# Ethernet.net
KiCad netlist of a schematic drawn in Altium Designer
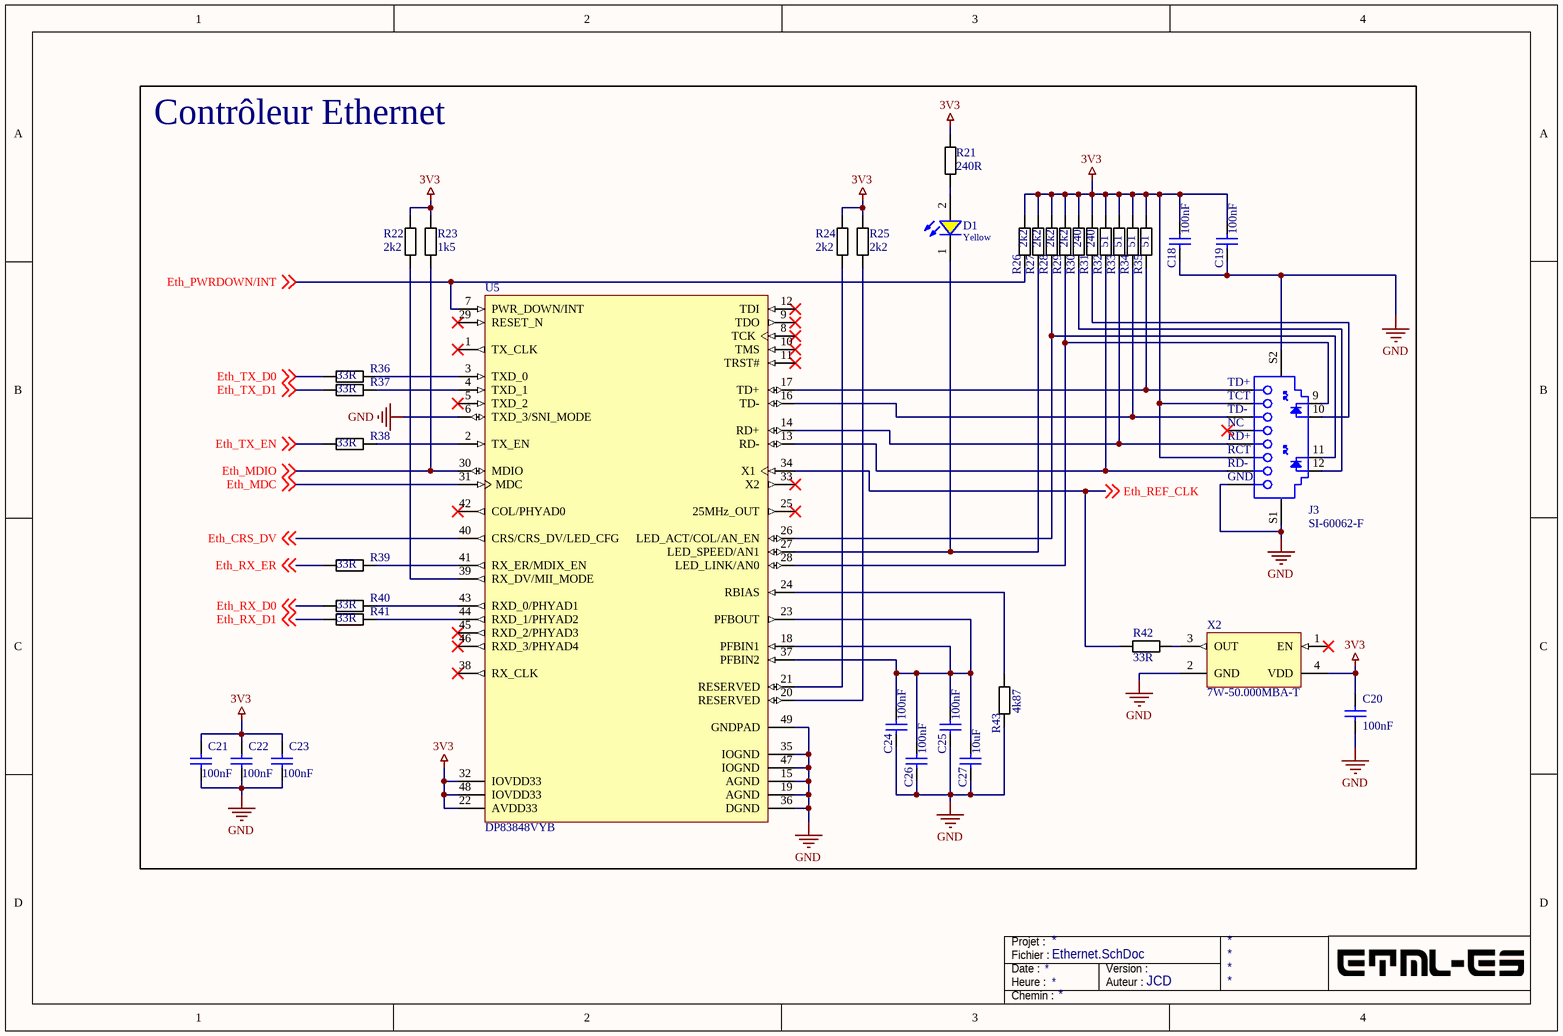
[diagram p0: Ethernet.SchDoc]

(export (version "E")
  (design (tool "Eeschema 10.0.6"))
  (components
    (comp (ref "C18")
      (value "100nF")
      (footprint "C0805")
      (description "Capacitor")
      (fields (field (name "PUBLISHER") "Altium Limited"))
      (libsource (lib "Miscellaneous Devices") (part "Cap"))
    )
    (comp (ref "C19")
      (value "100nF")
      (footprint "C0805")
      (description "Capacitor")
      (fields (field (name "PUBLISHER") "Altium Limited"))
      (libsource (lib "Miscellaneous Devices") (part "Cap"))
    )
    (comp (ref "C20")
      (value "100nF")
      (footprint "C0805")
      (description "Capacitor")
      (fields (field (name "PUBLISHER") "Altium Limited"))
      (libsource (lib "Miscellaneous Devices") (part "Cap"))
    )
    (comp (ref "C21")
      (value "100nF")
      (footprint "C0805")
      (description "Capacitor")
      (fields (field (name "PUBLISHER") "Altium Limited"))
      (libsource (lib "Miscellaneous Devices") (part "Cap"))
    )
    (comp (ref "C22")
      (value "100nF")
      (footprint "C0805")
      (description "Capacitor")
      (fields (field (name "PUBLISHER") "Altium Limited"))
      (libsource (lib "Miscellaneous Devices") (part "Cap"))
    )
    (comp (ref "C23")
      (value "100nF")
      (footprint "C0805")
      (description "Capacitor")
      (fields (field (name "PUBLISHER") "Altium Limited"))
      (libsource (lib "Miscellaneous Devices") (part "Cap"))
    )
    (comp (ref "C24")
      (value "100nF")
      (footprint "C0805")
      (description "Capacitor")
      (fields (field (name "PUBLISHER") "Altium Limited"))
      (libsource (lib "Miscellaneous Devices") (part "Cap"))
    )
    (comp (ref "C25")
      (value "100nF")
      (footprint "C0805")
      (description "Capacitor")
      (fields (field (name "PUBLISHER") "Altium Limited"))
      (libsource (lib "Miscellaneous Devices") (part "Cap"))
    )
    (comp (ref "C26")
      (value "100nF")
      (footprint "C0805")
      (description "Capacitor")
      (fields (field (name "PUBLISHER") "Altium Limited"))
      (libsource (lib "Miscellaneous Devices") (part "Cap"))
    )
    (comp (ref "C27")
      (value "10uF")
      (footprint "C0805")
      (description "Capacitor")
      (fields (field (name "PUBLISHER") "Altium Limited"))
      (libsource (lib "Miscellaneous Devices") (part "Cap"))
    )
    (comp (ref "D1")
      (value "Yellow")
      (footprint "WL-SMCW_0805")
      (description "SMT Mono-color Chip LED Waterclear WL-SMCW, size 0805, Yellow, 2 V, 140 deg, 120 mcd")
      (fields (field (name "PART NUMBER") "150080YS75000") (field (name "PUBLISHER") "Wurth Elektronik"))
      (libsource (lib "ALTIUM-WL-SMCW-rev18c") (part "150080YS75000"))
    )
    (comp (ref "J3")
      (value "SI-60062-F")
      (footprint "BELF-SI-60062-F_V")
      (description "1 Port RJ45 Magjack Connector with Yellow and Green LED, 10/100 Base-T, 12-Pin THD, RoHS, Tray")
      (fields (field (name "MANUFACTURER") "Bel Fuse"))
      (libsource (lib "Altium Content Vault") (part "RJ45-12-2SHLD"))
    )
    (comp (ref "R21")
      (value "240R")
      (footprint "RESC0805(2012)_L")
      (libsource (lib "LibComposant1819") (part "Resistance"))
    )
    (comp (ref "R22")
      (value "2k2")
      (footprint "RESC0805(2012)_L")
      (libsource (lib "LibComposant1819") (part "Resistance"))
    )
    (comp (ref "R23")
      (value "1k5")
      (footprint "RESC0805(2012)_L")
      (libsource (lib "LibComposant1819") (part "Resistance"))
    )
    (comp (ref "R24")
      (value "2k2")
      (footprint "RESC0805(2012)_L")
      (libsource (lib "LibComposant1819") (part "Resistance"))
    )
    (comp (ref "R25")
      (value "2k2")
      (footprint "RESC0805(2012)_L")
      (libsource (lib "LibComposant1819") (part "Resistance"))
    )
    (comp (ref "R26")
      (value "2k2")
      (footprint "RESC0805(2012)_L")
      (libsource (lib "LibComposant1819") (part "Resistance"))
    )
    (comp (ref "R27")
      (value "2k2")
      (footprint "RESC0805(2012)_L")
      (libsource (lib "LibComposant1819") (part "Resistance"))
    )
    (comp (ref "R28")
      (value "2k2")
      (footprint "RESC0805(2012)_L")
      (libsource (lib "LibComposant1819") (part "Resistance"))
    )
    (comp (ref "R29")
      (value "2k2")
      (footprint "RESC0805(2012)_L")
      (libsource (lib "LibComposant1819") (part "Resistance"))
    )
    (comp (ref "R30")
      (value "240")
      (footprint "RESC0805(2012)_L")
      (libsource (lib "LibComposant1819") (part "Resistance"))
    )
    (comp (ref "R31")
      (value "240")
      (footprint "RESC0805(2012)_L")
      (libsource (lib "LibComposant1819") (part "Resistance"))
    )
    (comp (ref "R32")
      (value "51")
      (footprint "RESC0805(2012)_L")
      (libsource (lib "LibComposant1819") (part "Resistance"))
    )
    (comp (ref "R33")
      (value "51")
      (footprint "RESC0805(2012)_L")
      (libsource (lib "LibComposant1819") (part "Resistance"))
    )
    (comp (ref "R34")
      (value "51")
      (footprint "RESC0805(2012)_L")
      (libsource (lib "LibComposant1819") (part "Resistance"))
    )
    (comp (ref "R35")
      (value "51")
      (footprint "RESC0805(2012)_L")
      (libsource (lib "LibComposant1819") (part "Resistance"))
    )
    (comp (ref "R36") (value "33R") (footprint "RESC0805(2012)_L") (libsource (lib "") (part "Resistance_1")))
    (comp (ref "R37") (value "33R") (footprint "RESC0805(2012)_L") (libsource (lib "") (part "Resistance_1")))
    (comp (ref "R38") (value "33R") (footprint "RESC0805(2012)_L") (libsource (lib "") (part "Resistance_1")))
    (comp (ref "R39") (value "33R") (footprint "RESC0805(2012)_L") (libsource (lib "") (part "Resistance_1")))
    (comp (ref "R40") (value "33R") (footprint "RESC0805(2012)_L") (libsource (lib "") (part "Resistance_1")))
    (comp (ref "R41") (value "33R") (footprint "RESC0805(2012)_L") (libsource (lib "") (part "Resistance_1")))
    (comp (ref "R42") (value "33R") (footprint "RESC0805(2012)_L") (libsource (lib "") (part "Resistance_1")))
    (comp (ref "R43")
      (value "4k87")
      (footprint "RESC0805(2012)_L")
      (libsource (lib "LibComposant1819") (part "Resistance"))
    )
    (comp (ref "U5")
      (value "DP83848VYB")
      (footprint "DP83848")
      (libsource (lib "LibComposant1819") (part "IN-LNTX-DP83848VYB"))
    )
    (comp (ref "X2")
      (value "7W-50.000MBA-T")
      (footprint "TXC-L500W700H130-4_V")
      (description "OSC, 50.000 MHZ, ± 25 ppm, 3.3 V, SMT")
      (libsource (lib "Altium Content Vault") (part "TXC-7W-50_000MBA-T-4"))
    )
  )
  (nets
    (net (code "1") (name "3V3") (class "Default")
      (node (ref "C18") (pin "2") (pinfunction "2_2") (pintype "passive"))
      (node (ref "C19") (pin "2") (pinfunction "2_2") (pintype "passive"))
      (node (ref "C20") (pin "2") (pinfunction "2_2") (pintype "passive"))
      (node (ref "C21") (pin "2") (pinfunction "2_2") (pintype "passive"))
      (node (ref "C22") (pin "2") (pinfunction "2_2") (pintype "passive"))
      (node (ref "C23") (pin "2") (pinfunction "2_2") (pintype "passive"))
      (node (ref "J3") (pin "2") (pinfunction "TCT_2") (pintype "passive"))
      (node (ref "J3") (pin "6") (pinfunction "RCT_6") (pintype "passive"))
      (node (ref "R21") (pin "1") (pinfunction "1_1") (pintype "passive"))
      (node (ref "R22") (pin "1") (pinfunction "1_1") (pintype "passive"))
      (node (ref "R23") (pin "1") (pinfunction "1_1") (pintype "passive"))
      (node (ref "R24") (pin "1") (pinfunction "1_1") (pintype "passive"))
      (node (ref "R25") (pin "1") (pinfunction "1_1") (pintype "passive"))
      (node (ref "R26") (pin "1") (pinfunction "1_1") (pintype "passive"))
      (node (ref "R27") (pin "1") (pinfunction "1_1") (pintype "passive"))
      (node (ref "R28") (pin "1") (pinfunction "1_1") (pintype "passive"))
      (node (ref "R29") (pin "1") (pinfunction "1_1") (pintype "passive"))
      (node (ref "R30") (pin "1") (pinfunction "1_1") (pintype "passive"))
      (node (ref "R31") (pin "1") (pinfunction "1_1") (pintype "passive"))
      (node (ref "R32") (pin "1") (pinfunction "1_1") (pintype "passive"))
      (node (ref "R33") (pin "1") (pinfunction "1_1") (pintype "passive"))
      (node (ref "R34") (pin "1") (pinfunction "1_1") (pintype "passive"))
      (node (ref "R35") (pin "1") (pinfunction "1_1") (pintype "passive"))
      (node (ref "U5") (pin "22") (pinfunction "AVDD33_22") (pintype "power_in"))
      (node (ref "U5") (pin "32") (pinfunction "IOVDD33_32") (pintype "power_in"))
      (node (ref "U5") (pin "48") (pinfunction "IOVDD33_48") (pintype "power_in"))
      (node (ref "X2") (pin "4") (pinfunction "VDD_4") (pintype "power_in"))
    )
    (net (code "2") (name "Eth_CRS_DV") (class "Default")
      (node (ref "U5") (pin "40") (pinfunction "CRS/CRS_DV/LED_CFG_40") (pintype "output"))
    )
    (net (code "3") (name "Eth_MDC") (class "Default")
      (node (ref "U5") (pin "31") (pinfunction "MDC_31") (pintype "input"))
    )
    (net (code "4") (name "Eth_MDIO") (class "Default")
      (node (ref "R23") (pin "2") (pinfunction "2_2") (pintype "passive"))
      (node (ref "U5") (pin "30") (pinfunction "MDIO_30") (pintype "bidirectional"))
    )
    (net (code "5") (name "Eth_PWRDOWN{slash}INT") (class "Default")
      (node (ref "R26") (pin "2") (pinfunction "2_2") (pintype "passive"))
      (node (ref "U5") (pin "7") (pinfunction "PWR_DOWN/INT_7") (pintype "input"))
    )
    (net (code "6") (name "Eth_REF_CLK") (class "Default")
      (node (ref "R42") (pin "1") (pinfunction "1_1") (pintype "passive"))
      (node (ref "U5") (pin "34") (pinfunction "X1_34") (pintype "input"))
    )
    (net (code "7") (name "Eth_RX_D0") (class "Default")
      (node (ref "R40") (pin "1") (pinfunction "1_1") (pintype "passive"))
    )
    (net (code "8") (name "Eth_RX_D1") (class "Default")
      (node (ref "R41") (pin "1") (pinfunction "1_1") (pintype "passive"))
    )
    (net (code "9") (name "Eth_RX_ER") (class "Default")
      (node (ref "R39") (pin "1") (pinfunction "1_1") (pintype "passive"))
    )
    (net (code "10") (name "Eth_TX_D0") (class "Default")
      (node (ref "R36") (pin "1") (pinfunction "1_1") (pintype "passive"))
    )
    (net (code "11") (name "Eth_TX_D1") (class "Default")
      (node (ref "R37") (pin "1") (pinfunction "1_1") (pintype "passive"))
    )
    (net (code "12") (name "Eth_TX_EN") (class "Default")
      (node (ref "R38") (pin "1") (pinfunction "1_1") (pintype "passive"))
    )
    (net (code "13") (name "GND") (class "Default")
      (node (ref "C18") (pin "1") (pinfunction "1_1") (pintype "passive"))
      (node (ref "C19") (pin "1") (pinfunction "1_1") (pintype "passive"))
      (node (ref "C20") (pin "1") (pinfunction "1_1") (pintype "passive"))
      (node (ref "C21") (pin "1") (pinfunction "1_1") (pintype "passive"))
      (node (ref "C22") (pin "1") (pinfunction "1_1") (pintype "passive"))
      (node (ref "C23") (pin "1") (pinfunction "1_1") (pintype "passive"))
      (node (ref "C24") (pin "1") (pinfunction "1_1") (pintype "passive"))
      (node (ref "C25") (pin "1") (pinfunction "1_1") (pintype "passive"))
      (node (ref "C26") (pin "1") (pinfunction "1_1") (pintype "passive"))
      (node (ref "C27") (pin "1") (pinfunction "1_1") (pintype "passive"))
      (node (ref "J3") (pin "8") (pinfunction "GND_8") (pintype "passive"))
      (node (ref "J3") (pin "S1") (pinfunction "S1_S1") (pintype "passive"))
      (node (ref "J3") (pin "S2") (pinfunction "S2_S2") (pintype "passive"))
      (node (ref "R43") (pin "2") (pinfunction "2_2") (pintype "passive"))
      (node (ref "U5") (pin "15") (pinfunction "AGND_15") (pintype "power_in"))
      (node (ref "U5") (pin "19") (pinfunction "AGND_19") (pintype "power_in"))
      (node (ref "U5") (pin "35") (pinfunction "IOGND_35") (pintype "power_in"))
      (node (ref "U5") (pin "36") (pinfunction "DGND_36") (pintype "power_in"))
      (node (ref "U5") (pin "47") (pinfunction "IOGND_47") (pintype "power_in"))
      (node (ref "U5") (pin "49") (pinfunction "GNDPAD_49") (pintype "power_in"))
      (node (ref "U5") (pin "6") (pinfunction "TXD_3/SNI_MODE_6") (pintype "bidirectional"))
      (node (ref "X2") (pin "2") (pinfunction "GND_2") (pintype "power_in"))
    )
    (net (code "14") (name "Net-(D1-A)") (class "Default")
      (node (ref "D1") (pin "2") (pinfunction "A_2") (pintype "passive"))
      (node (ref "R21") (pin "2") (pinfunction "2_2") (pintype "passive"))
    )
    (net (code "15") (name "Net-(D1-K)") (class "Default")
      (node (ref "D1") (pin "1") (pinfunction "K_1") (pintype "passive"))
      (node (ref "R27") (pin "2") (pinfunction "2_2") (pintype "passive"))
      (node (ref "U5") (pin "27") (pinfunction "LED_SPEED/AN1_27") (pintype "bidirectional"))
    )
    (net (code "16") (name "Net-(J3-Pad10)") (class "Default")
      (node (ref "J3") (pin "10") (pinfunction "10_10") (pintype "passive"))
      (node (ref "R31") (pin "2") (pinfunction "2_2") (pintype "passive"))
    )
    (net (code "17") (name "Net-(J3-Pad12)") (class "Default")
      (node (ref "J3") (pin "12") (pinfunction "12_12") (pintype "passive"))
      (node (ref "R30") (pin "2") (pinfunction "2_2") (pintype "passive"))
    )
    (net (code "18") (name "Net-(J3-RD+)") (class "Default")
      (node (ref "J3") (pin "5") (pinfunction "RD+_5") (pintype "passive"))
      (node (ref "R33") (pin "2") (pinfunction "2_2") (pintype "passive"))
      (node (ref "U5") (pin "14") (pinfunction "RD+_14") (pintype "bidirectional"))
    )
    (net (code "19") (name "Net-(J3-RD-)") (class "Default")
      (node (ref "J3") (pin "7") (pinfunction "RD-_7") (pintype "passive"))
      (node (ref "R32") (pin "2") (pinfunction "2_2") (pintype "passive"))
      (node (ref "U5") (pin "13") (pinfunction "RD-_13") (pintype "bidirectional"))
    )
    (net (code "20") (name "Net-(J3-TD+)") (class "Default")
      (node (ref "J3") (pin "1") (pinfunction "TD+_1") (pintype "passive"))
      (node (ref "R35") (pin "2") (pinfunction "2_2") (pintype "passive"))
      (node (ref "U5") (pin "17") (pinfunction "TD+_17") (pintype "bidirectional"))
    )
    (net (code "21") (name "Net-(J3-TD-)") (class "Default")
      (node (ref "J3") (pin "3") (pinfunction "TD-_3") (pintype "passive"))
      (node (ref "R34") (pin "2") (pinfunction "2_2") (pintype "passive"))
      (node (ref "U5") (pin "16") (pinfunction "TD-_16") (pintype "bidirectional"))
    )
    (net (code "22") (name "Net-(R24-Pad2)") (class "Default")
      (node (ref "R24") (pin "2") (pinfunction "2_2") (pintype "passive"))
      (node (ref "U5") (pin "21") (pinfunction "RESERVED_21") (pintype "bidirectional"))
    )
    (net (code "23") (name "Net-(R25-Pad2)") (class "Default")
      (node (ref "R25") (pin "2") (pinfunction "2_2") (pintype "passive"))
      (node (ref "U5") (pin "20") (pinfunction "RESERVED_20") (pintype "bidirectional"))
    )
    (net (code "24") (name "Net-(U5-LED_ACT{slash}COL{slash}AN_EN)") (class "Default")
      (node (ref "J3") (pin "11") (pinfunction "11_11") (pintype "passive"))
      (node (ref "R28") (pin "2") (pinfunction "2_2") (pintype "passive"))
      (node (ref "U5") (pin "26") (pinfunction "LED_ACT/COL/AN_EN_26") (pintype "bidirectional"))
    )
    (net (code "25") (name "Net-(U5-LED_LINK{slash}AN0)") (class "Default")
      (node (ref "J3") (pin "9") (pinfunction "9_9") (pintype "passive"))
      (node (ref "R29") (pin "2") (pinfunction "2_2") (pintype "passive"))
      (node (ref "U5") (pin "28") (pinfunction "LED_LINK/AN0_28") (pintype "bidirectional"))
    )
    (net (code "26") (name "Net-(U5-PFBIN1)") (class "Default")
      (node (ref "C24") (pin "2") (pinfunction "2_2") (pintype "passive"))
      (node (ref "C25") (pin "2") (pinfunction "2_2") (pintype "passive"))
      (node (ref "C26") (pin "2") (pinfunction "2_2") (pintype "passive"))
      (node (ref "C27") (pin "2") (pinfunction "2_2") (pintype "passive"))
      (node (ref "U5") (pin "18") (pinfunction "PFBIN1_18") (pintype "input"))
      (node (ref "U5") (pin "23") (pinfunction "PFBOUT_23") (pintype "output"))
      (node (ref "U5") (pin "37") (pinfunction "PFBIN2_37") (pintype "input"))
    )
    (net (code "27") (name "Net-(U5-RBIAS)") (class "Default")
      (node (ref "R43") (pin "1") (pinfunction "1_1") (pintype "passive"))
      (node (ref "U5") (pin "24") (pinfunction "RBIAS_24") (pintype "input"))
    )
    (net (code "28") (name "Net-(U5-RXD_0{slash}PHYAD1)") (class "Default")
      (node (ref "R40") (pin "2") (pinfunction "2_2") (pintype "passive"))
      (node (ref "U5") (pin "43") (pinfunction "RXD_0/PHYAD1_43") (pintype "output"))
    )
    (net (code "29") (name "Net-(U5-RXD_1{slash}PHYAD2)") (class "Default")
      (node (ref "R41") (pin "2") (pinfunction "2_2") (pintype "passive"))
      (node (ref "U5") (pin "44") (pinfunction "RXD_1/PHYAD2_44") (pintype "output"))
    )
    (net (code "30") (name "Net-(U5-RX_DV{slash}MII_MODE)") (class "Default")
      (node (ref "R22") (pin "2") (pinfunction "2_2") (pintype "passive"))
      (node (ref "U5") (pin "39") (pinfunction "RX_DV/MII_MODE_39") (pintype "output"))
    )
    (net (code "31") (name "Net-(U5-RX_ER{slash}MDIX_EN)") (class "Default")
      (node (ref "R39") (pin "2") (pinfunction "2_2") (pintype "passive"))
      (node (ref "U5") (pin "41") (pinfunction "RX_ER/MDIX_EN_41") (pintype "output"))
    )
    (net (code "32") (name "Net-(U5-TXD_0)") (class "Default")
      (node (ref "R36") (pin "2") (pinfunction "2_2") (pintype "passive"))
      (node (ref "U5") (pin "3") (pinfunction "TXD_0_3") (pintype "input"))
    )
    (net (code "33") (name "Net-(U5-TXD_1)") (class "Default")
      (node (ref "R37") (pin "2") (pinfunction "2_2") (pintype "passive"))
      (node (ref "U5") (pin "4") (pinfunction "TXD_1_4") (pintype "input"))
    )
    (net (code "34") (name "Net-(U5-TX_EN)") (class "Default")
      (node (ref "R38") (pin "2") (pinfunction "2_2") (pintype "passive"))
      (node (ref "U5") (pin "2") (pinfunction "TX_EN_2") (pintype "input"))
    )
    (net (code "35") (name "Net-(X2-OUT)") (class "Default")
      (node (ref "R42") (pin "2") (pinfunction "2_2") (pintype "passive"))
      (node (ref "X2") (pin "3") (pinfunction "OUT_3") (pintype "output"))
    )
    (net (code "36") (name "unconnected-(J3-NC-Pad4)") (class "Default")
      (node (ref "J3") (pin "4") (pinfunction "NC_4") (pintype "passive+no_connect"))
    )
    (net (code "37") (name "unconnected-(U5-25MHz_OUT-Pad25)") (class "Default")
      (node (ref "U5") (pin "25") (pinfunction "25MHz_OUT_25") (pintype "output+no_connect"))
    )
    (net (code "38") (name "unconnected-(U5-COL{slash}PHYAD0-Pad42)") (class "Default")
      (node (ref "U5") (pin "42") (pinfunction "COL/PHYAD0_42") (pintype "output+no_connect"))
    )
    (net (code "39") (name "unconnected-(U5-RESET_N-Pad29)") (class "Default")
      (node (ref "U5") (pin "29") (pinfunction "RESET_N_29") (pintype "input+no_connect"))
    )
    (net (code "40") (name "unconnected-(U5-RXD_2{slash}PHYAD3-Pad45)") (class "Default")
      (node (ref "U5") (pin "45") (pinfunction "RXD_2/PHYAD3_45") (pintype "output+no_connect"))
    )
    (net (code "41") (name "unconnected-(U5-RXD_3{slash}PHYAD4-Pad46)") (class "Default")
      (node (ref "U5") (pin "46") (pinfunction "RXD_3/PHYAD4_46") (pintype "output+no_connect"))
    )
    (net (code "42") (name "unconnected-(U5-RX_CLK-Pad38)") (class "Default")
      (node (ref "U5") (pin "38") (pinfunction "RX_CLK_38") (pintype "output+no_connect"))
    )
    (net (code "43") (name "unconnected-(U5-TCK-Pad8)") (class "Default")
      (node (ref "U5") (pin "8") (pinfunction "TCK_8") (pintype "input+no_connect"))
    )
    (net (code "44") (name "unconnected-(U5-TDI-Pad12)") (class "Default")
      (node (ref "U5") (pin "12") (pinfunction "TDI_12") (pintype "input+no_connect"))
    )
    (net (code "45") (name "unconnected-(U5-TDO-Pad9)") (class "Default")
      (node (ref "U5") (pin "9") (pinfunction "TDO_9") (pintype "output+no_connect"))
    )
    (net (code "46") (name "unconnected-(U5-TMS-Pad10)") (class "Default")
      (node (ref "U5") (pin "10") (pinfunction "TMS_10") (pintype "input+no_connect"))
    )
    (net (code "47") (name "unconnected-(U5-TRST#-Pad11)") (class "Default")
      (node (ref "U5") (pin "11") (pinfunction "TRST#_11") (pintype "input+no_connect"))
    )
    (net (code "48") (name "unconnected-(U5-TXD_2-Pad5)") (class "Default")
      (node (ref "U5") (pin "5") (pinfunction "TXD_2_5") (pintype "input+no_connect"))
    )
    (net (code "49") (name "unconnected-(U5-TX_CLK-Pad1)") (class "Default")
      (node (ref "U5") (pin "1") (pinfunction "TX_CLK_1") (pintype "output+no_connect"))
    )
    (net (code "50") (name "unconnected-(U5-X2-Pad33)") (class "Default")
      (node (ref "U5") (pin "33") (pinfunction "X2_33") (pintype "output+no_connect"))
    )
    (net (code "51") (name "unconnected-(X2-EN-Pad1)") (class "Default")
      (node (ref "X2") (pin "1") (pinfunction "EN_1") (pintype "input+no_connect"))
    )
  )
)
